# soundMeter_sm.net
KiCad netlist of a schematic drawn in EAGLE
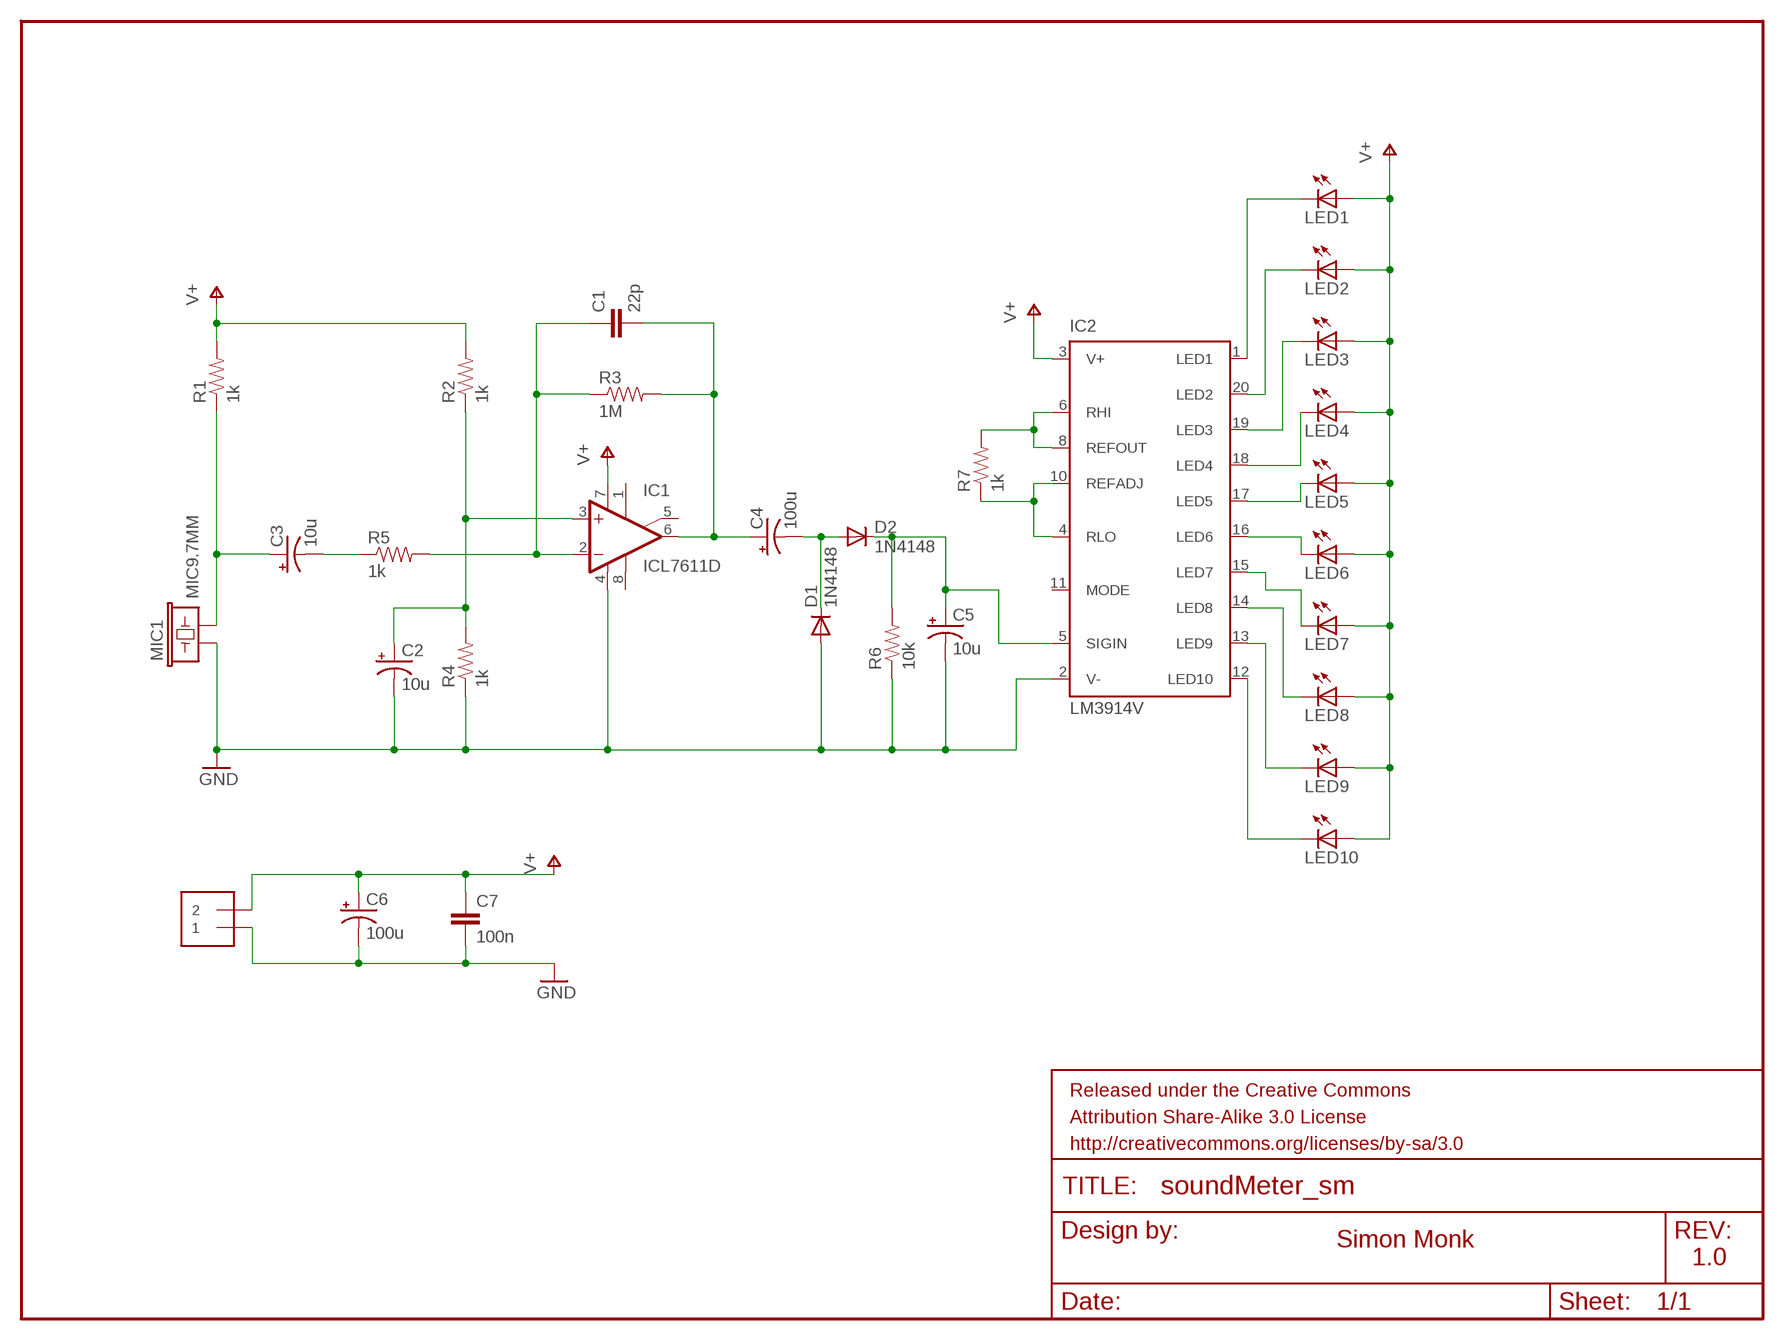
[diagram p0: schematic, sheet 1]

(export (version "E")
  (design (tool "Eeschema 10.0.6"))
  (components
    (comp (ref "C1")
      (value "22p")
      (footprint "eagle-import:1206")
      (libsource (lib "eagle-import") (part "CAP1206"))
    )
    (comp (ref "C2")
      (value "10u")
      (footprint "eagle-import:PANASONIC_C")
      (libsource (lib "eagle-import") (part "CAP_POLC"))
    )
    (comp (ref "C3")
      (value "10u")
      (footprint "eagle-import:PANASONIC_C")
      (libsource (lib "eagle-import") (part "CAP_POLC"))
    )
    (comp (ref "C4")
      (value "100u")
      (footprint "eagle-import:PANASONIC_D")
      (libsource (lib "eagle-import") (part "CAP_POLD"))
    )
    (comp (ref "C5")
      (value "10u")
      (footprint "eagle-import:PANASONIC_C")
      (libsource (lib "eagle-import") (part "CAP_POLC"))
    )
    (comp (ref "C6")
      (value "100u")
      (footprint "eagle-import:PANASONIC_D")
      (libsource (lib "eagle-import") (part "CAP_POLD"))
    )
    (comp (ref "C7")
      (value "100n")
      (footprint "eagle-import:1206")
      (libsource (lib "eagle-import") (part "CAP1206"))
    )
    (comp (ref "D1")
      (value "1N4148")
      (footprint "eagle-import:SOD-323")
      (libsource (lib "eagle-import") (part "DIODESOD"))
    )
    (comp (ref "D2")
      (value "1N4148")
      (footprint "eagle-import:SOD-323")
      (libsource (lib "eagle-import") (part "DIODESOD"))
    )
    (comp (ref "FRAME1")
      (value "FRAME-LETTER")
      (footprint "eagle-import:CREATIVE_COMMONS")
      (libsource (lib "eagle-import") (part "FRAME-LETTER"))
    )
    (comp (ref "IC1")
      (value "ICL7611D")
      (footprint "eagle-import:SO08")
      (libsource (lib "eagle-import") (part "ICL7611D"))
    )
    (comp (ref "IC2")
      (value "LM3914V")
      (footprint "eagle-import:PLCC20S")
      (libsource (lib "eagle-import") (part "LM391V4"))
    )
    (comp (ref "J1")
      (value "1X2-3.5MM")
      (footprint "eagle-import:1X2-3.5MM")
      (libsource (lib "eagle-import") (part "1X2-3.5MM"))
    )
    (comp (ref "LED1")
      (value "LED1206")
      (footprint "eagle-import:LED-1206")
      (libsource (lib "eagle-import") (part "LED1206"))
    )
    (comp (ref "LED2")
      (value "LED1206")
      (footprint "eagle-import:LED-1206")
      (libsource (lib "eagle-import") (part "LED1206"))
    )
    (comp (ref "LED3")
      (value "LED1206")
      (footprint "eagle-import:LED-1206")
      (libsource (lib "eagle-import") (part "LED1206"))
    )
    (comp (ref "LED4")
      (value "LED1206")
      (footprint "eagle-import:LED-1206")
      (libsource (lib "eagle-import") (part "LED1206"))
    )
    (comp (ref "LED5")
      (value "LED1206")
      (footprint "eagle-import:LED-1206")
      (libsource (lib "eagle-import") (part "LED1206"))
    )
    (comp (ref "LED6")
      (value "LED1206")
      (footprint "eagle-import:LED-1206")
      (libsource (lib "eagle-import") (part "LED1206"))
    )
    (comp (ref "LED7")
      (value "LED1206")
      (footprint "eagle-import:LED-1206")
      (libsource (lib "eagle-import") (part "LED1206"))
    )
    (comp (ref "LED8")
      (value "LED1206")
      (footprint "eagle-import:LED-1206")
      (libsource (lib "eagle-import") (part "LED1206"))
    )
    (comp (ref "LED9")
      (value "LED1206")
      (footprint "eagle-import:LED-1206")
      (libsource (lib "eagle-import") (part "LED1206"))
    )
    (comp (ref "LED10")
      (value "LED1206")
      (footprint "eagle-import:LED-1206")
      (libsource (lib "eagle-import") (part "LED1206"))
    )
    (comp (ref "MIC1")
      (value "MIC9.7MM")
      (footprint "eagle-import:MIC-9.7MM")
      (libsource (lib "eagle-import") (part "MIC9.7MM"))
    )
    (comp (ref "R1")
      (value "1k")
      (footprint "eagle-import:1206")
      (libsource (lib "eagle-import") (part "RESISTOR1206"))
    )
    (comp (ref "R2")
      (value "1k")
      (footprint "eagle-import:1206")
      (libsource (lib "eagle-import") (part "RESISTOR1206"))
    )
    (comp (ref "R3")
      (value "1M")
      (footprint "eagle-import:1206")
      (libsource (lib "eagle-import") (part "RESISTOR1206"))
    )
    (comp (ref "R4")
      (value "1k")
      (footprint "eagle-import:1206")
      (libsource (lib "eagle-import") (part "RESISTOR1206"))
    )
    (comp (ref "R5")
      (value "1k")
      (footprint "eagle-import:1206")
      (libsource (lib "eagle-import") (part "RESISTOR1206"))
    )
    (comp (ref "R6")
      (value "10k")
      (footprint "eagle-import:1206")
      (libsource (lib "eagle-import") (part "RESISTOR1206"))
    )
    (comp (ref "R7")
      (value "1k")
      (footprint "eagle-import:1206")
      (libsource (lib "eagle-import") (part "RESISTOR1206"))
    )
  )
  (nets
    (net (code "1") (name "GND") (class "Default")
      (node (ref "C2") (pin "-") (pinfunction "-_-") (pintype "passive"))
      (node (ref "C5") (pin "-") (pinfunction "-_-") (pintype "passive"))
      (node (ref "C6") (pin "-") (pinfunction "-_-") (pintype "passive"))
      (node (ref "C7") (pin "2") (pinfunction "2_2") (pintype "passive"))
      (node (ref "D1") (pin "2") (pinfunction "A_2") (pintype "passive"))
      (node (ref "IC1") (pin "4") (pinfunction "V-_4") (pintype "power_in"))
      (node (ref "IC2") (pin "2") (pinfunction "V-_2") (pintype "power_in"))
      (node (ref "J1") (pin "1") (pinfunction "1_1") (pintype "passive"))
      (node (ref "MIC1") (pin "1") (pinfunction "1_1") (pintype "passive"))
      (node (ref "R4") (pin "1") (pinfunction "1_1") (pintype "passive"))
      (node (ref "R6") (pin "1") (pinfunction "1_1") (pintype "passive"))
    )
    (net (code "2") (name "Net-(C3-Pad+)") (class "Default")
      (node (ref "C3") (pin "+") (pinfunction "+_+") (pintype "passive"))
      (node (ref "MIC1") (pin "2") (pinfunction "2_2") (pintype "passive"))
      (node (ref "R1") (pin "1") (pinfunction "1_1") (pintype "passive"))
    )
    (net (code "3") (name "Net-(C3-Pad-)") (class "Default")
      (node (ref "C3") (pin "-") (pinfunction "-_-") (pintype "passive"))
      (node (ref "R5") (pin "1") (pinfunction "1_1") (pintype "passive"))
    )
    (net (code "4") (name "Net-(D1-C)") (class "Default")
      (node (ref "C4") (pin "-") (pinfunction "-_-") (pintype "passive"))
      (node (ref "D1") (pin "1") (pinfunction "C_1") (pintype "passive"))
      (node (ref "D2") (pin "2") (pinfunction "A_2") (pintype "passive"))
    )
    (net (code "5") (name "Net-(D2-C)") (class "Default")
      (node (ref "C5") (pin "+") (pinfunction "+_+") (pintype "passive"))
      (node (ref "D2") (pin "1") (pinfunction "C_1") (pintype "passive"))
      (node (ref "IC2") (pin "5") (pinfunction "SIGIN_5") (pintype "input"))
      (node (ref "R6") (pin "2") (pinfunction "2_2") (pintype "passive"))
    )
    (net (code "6") (name "Net-(IC1-+IN)") (class "Default")
      (node (ref "C2") (pin "+") (pinfunction "+_+") (pintype "passive"))
      (node (ref "IC1") (pin "3") (pinfunction "+IN_3") (pintype "input"))
      (node (ref "R2") (pin "1") (pinfunction "1_1") (pintype "passive"))
      (node (ref "R4") (pin "2") (pinfunction "2_2") (pintype "passive"))
    )
    (net (code "7") (name "Net-(IC1--IN)") (class "Default")
      (node (ref "C1") (pin "1") (pinfunction "1_1") (pintype "passive"))
      (node (ref "IC1") (pin "2") (pinfunction "-IN_2") (pintype "input"))
      (node (ref "R3") (pin "1") (pinfunction "1_1") (pintype "passive"))
      (node (ref "R5") (pin "2") (pinfunction "2_2") (pintype "passive"))
    )
    (net (code "8") (name "Net-(IC1-OUT)") (class "Default")
      (node (ref "C1") (pin "2") (pinfunction "2_2") (pintype "passive"))
      (node (ref "C4") (pin "+") (pinfunction "+_+") (pintype "passive"))
      (node (ref "IC1") (pin "6") (pinfunction "OUT_6") (pintype "output"))
      (node (ref "R3") (pin "2") (pinfunction "2_2") (pintype "passive"))
    )
    (net (code "9") (name "Net-(IC2-LED1)") (class "Default")
      (node (ref "IC2") (pin "1") (pinfunction "LED1_1") (pintype "output"))
      (node (ref "LED1") (pin "C") (pinfunction "C_C") (pintype "passive"))
    )
    (net (code "10") (name "Net-(IC2-LED2)") (class "Default")
      (node (ref "IC2") (pin "20") (pinfunction "LED2_20") (pintype "output"))
      (node (ref "LED2") (pin "C") (pinfunction "C_C") (pintype "passive"))
    )
    (net (code "11") (name "Net-(IC2-LED3)") (class "Default")
      (node (ref "IC2") (pin "19") (pinfunction "LED3_19") (pintype "output"))
      (node (ref "LED3") (pin "C") (pinfunction "C_C") (pintype "passive"))
    )
    (net (code "12") (name "Net-(IC2-LED4)") (class "Default")
      (node (ref "IC2") (pin "18") (pinfunction "LED4_18") (pintype "output"))
      (node (ref "LED4") (pin "C") (pinfunction "C_C") (pintype "passive"))
    )
    (net (code "13") (name "Net-(IC2-LED5)") (class "Default")
      (node (ref "IC2") (pin "17") (pinfunction "LED5_17") (pintype "output"))
      (node (ref "LED5") (pin "C") (pinfunction "C_C") (pintype "passive"))
    )
    (net (code "14") (name "Net-(IC2-LED6)") (class "Default")
      (node (ref "IC2") (pin "16") (pinfunction "LED6_16") (pintype "output"))
      (node (ref "LED6") (pin "C") (pinfunction "C_C") (pintype "passive"))
    )
    (net (code "15") (name "Net-(IC2-LED7)") (class "Default")
      (node (ref "IC2") (pin "15") (pinfunction "LED7_15") (pintype "output"))
      (node (ref "LED7") (pin "C") (pinfunction "C_C") (pintype "passive"))
    )
    (net (code "16") (name "Net-(IC2-LED8)") (class "Default")
      (node (ref "IC2") (pin "14") (pinfunction "LED8_14") (pintype "output"))
      (node (ref "LED8") (pin "C") (pinfunction "C_C") (pintype "passive"))
    )
    (net (code "17") (name "Net-(IC2-LED9)") (class "Default")
      (node (ref "IC2") (pin "13") (pinfunction "LED9_13") (pintype "output"))
      (node (ref "LED9") (pin "C") (pinfunction "C_C") (pintype "passive"))
    )
    (net (code "18") (name "Net-(IC2-LED10)") (class "Default")
      (node (ref "IC2") (pin "12") (pinfunction "LED10_12") (pintype "output"))
      (node (ref "LED10") (pin "C") (pinfunction "C_C") (pintype "passive"))
    )
    (net (code "19") (name "Net-(IC2-REFADJ)") (class "Default")
      (node (ref "IC2") (pin "10") (pinfunction "REFADJ_10") (pintype "passive"))
      (node (ref "IC2") (pin "4") (pinfunction "RLO_4") (pintype "input"))
      (node (ref "R7") (pin "1") (pinfunction "1_1") (pintype "passive"))
    )
    (net (code "20") (name "Net-(IC2-REFOUT)") (class "Default")
      (node (ref "IC2") (pin "6") (pinfunction "RHI_6") (pintype "input"))
      (node (ref "IC2") (pin "8") (pinfunction "REFOUT_8") (pintype "output"))
      (node (ref "R7") (pin "2") (pinfunction "2_2") (pintype "passive"))
    )
    (net (code "21") (name "V+") (class "Default")
      (node (ref "C6") (pin "+") (pinfunction "+_+") (pintype "passive"))
      (node (ref "C7") (pin "1") (pinfunction "1_1") (pintype "passive"))
      (node (ref "IC1") (pin "7") (pinfunction "V+_7") (pintype "power_in"))
      (node (ref "IC2") (pin "3") (pinfunction "V+_3") (pintype "power_in"))
      (node (ref "J1") (pin "2") (pinfunction "2_2") (pintype "passive"))
      (node (ref "LED1") (pin "A") (pinfunction "A_A") (pintype "passive"))
      (node (ref "LED10") (pin "A") (pinfunction "A_A") (pintype "passive"))
      (node (ref "LED2") (pin "A") (pinfunction "A_A") (pintype "passive"))
      (node (ref "LED3") (pin "A") (pinfunction "A_A") (pintype "passive"))
      (node (ref "LED4") (pin "A") (pinfunction "A_A") (pintype "passive"))
      (node (ref "LED5") (pin "A") (pinfunction "A_A") (pintype "passive"))
      (node (ref "LED6") (pin "A") (pinfunction "A_A") (pintype "passive"))
      (node (ref "LED7") (pin "A") (pinfunction "A_A") (pintype "passive"))
      (node (ref "LED8") (pin "A") (pinfunction "A_A") (pintype "passive"))
      (node (ref "LED9") (pin "A") (pinfunction "A_A") (pintype "passive"))
      (node (ref "R1") (pin "2") (pinfunction "2_2") (pintype "passive"))
      (node (ref "R2") (pin "2") (pinfunction "2_2") (pintype "passive"))
    )
    (net (code "22") (name "unconnected-(IC1-ON1-Pad1)") (class "Default")
      (node (ref "IC1") (pin "1") (pinfunction "ON1_1") (pintype "passive"))
    )
    (net (code "23") (name "unconnected-(IC1-ON2-Pad5)") (class "Default")
      (node (ref "IC1") (pin "5") (pinfunction "ON2_5") (pintype "passive"))
    )
    (net (code "24") (name "unconnected-(IC1-OPT-Pad8)") (class "Default")
      (node (ref "IC1") (pin "8") (pinfunction "OPT_8") (pintype "passive"))
    )
    (net (code "25") (name "unconnected-(IC2-MODE-Pad11)") (class "Default")
      (node (ref "IC2") (pin "11") (pinfunction "MODE_11") (pintype "input"))
    )
  )
)
